# UBX_NORA_B1_SCHEM_0003_Shield_Conn.net
KiCad netlist of a schematic drawn in Altium Designer
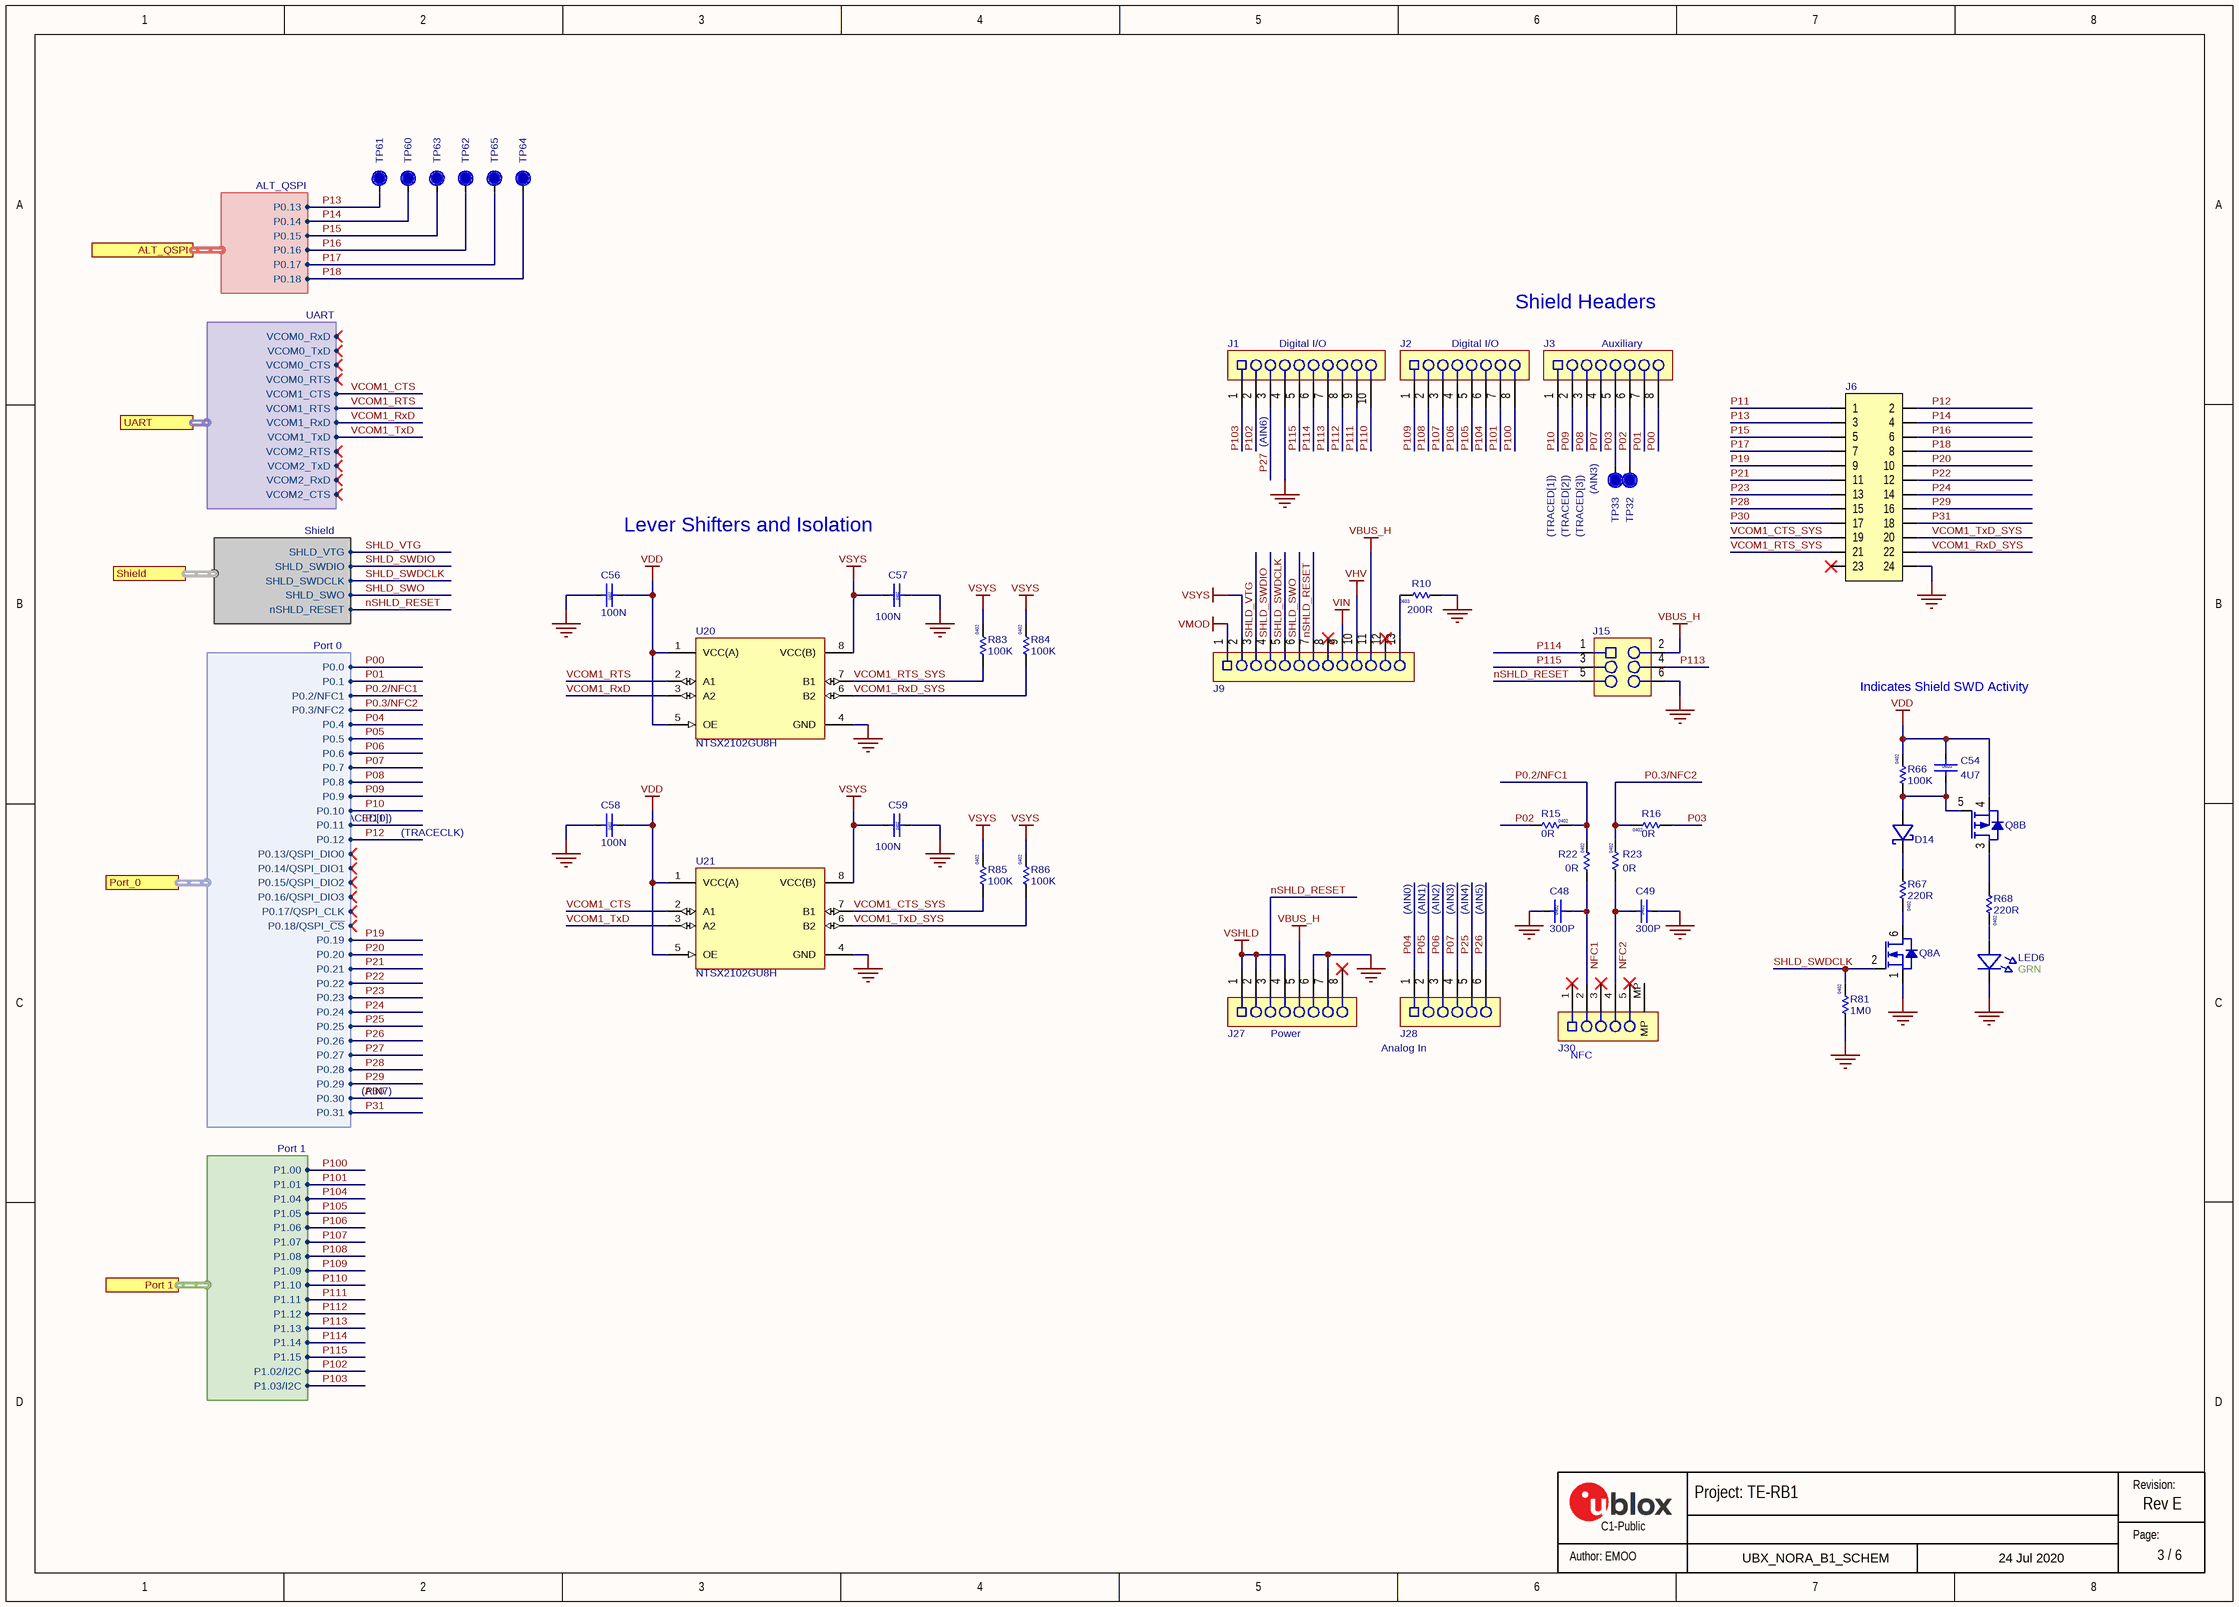
[diagram p0: UBX_NORA_B1_SCHEM_0003_Shield_Conn.SchDoc]

(export (version "E")
  (design (tool "Eeschema 10.0.6"))
  (components
    (comp (ref "C48")
      (value "300P")
      (footprint "Cap 0402 HD")
      (description "CAP CER C0G 0402 300P 50V")
      (fields
        (field (name "SIZE") "0402")
        (field (name "PART NUMBER") "UBXH01-0000594")
        (field (name "MANUFACTURER") "Murata Manufacturing Company, Ltd.")
        (field (name "EDITOR") "eric.moog")
      )
      (libsource (lib "UBX_Parts_DB_Lib") (part "Cap Chip"))
    )
    (comp (ref "C49")
      (value "300P")
      (footprint "Cap 0402 HD")
      (description "CAP CER C0G 0402 300P 50V")
      (fields
        (field (name "SIZE") "0402")
        (field (name "PART NUMBER") "UBXH01-0000594")
        (field (name "MANUFACTURER") "Murata Manufacturing Company, Ltd.")
        (field (name "EDITOR") "eric.moog")
      )
      (libsource (lib "UBX_Parts_DB_Lib") (part "Cap Chip"))
    )
    (comp (ref "C54")
      (value "4U7")
      (footprint "CAP 0603 HD")
      (description "CAP CER X5R 0603 4U7 10% 6.3V")
      (fields
        (field (name "SIZE") "0603")
        (field (name "PART NUMBER") "UBXH01-2002003")
        (field (name "TOLERANCE") "10%")
        (field (name "EDITOR") "philippe.largier")
        (field (name "RELEASED BY") "roland.rust")
      )
      (libsource (lib "UBX_Parts_DB_Lib") (part "Cap Chip"))
    )
    (comp (ref "C56")
      (value "100N")
      (footprint "Cap 0402 HD")
      (description "CAP CER X5R 0402 100N 10% 10V")
      (fields
        (field (name "SIZE") "0402")
        (field (name "PART NUMBER") "UBXH01-2021002")
        (field (name "TOLERANCE") "10%")
        (field (name "EDITOR") "roland.rust")
        (field (name "RELEASED BY") "roland.rust")
      )
      (libsource (lib "UBX_Parts_DB_Lib") (part "Cap Chip"))
    )
    (comp (ref "C57")
      (value "100N")
      (footprint "Cap 0402 HD")
      (description "CAP CER X5R 0402 100N 10% 10V")
      (fields
        (field (name "SIZE") "0402")
        (field (name "PART NUMBER") "UBXH01-2021002")
        (field (name "TOLERANCE") "10%")
        (field (name "EDITOR") "roland.rust")
        (field (name "RELEASED BY") "roland.rust")
      )
      (libsource (lib "UBX_Parts_DB_Lib") (part "Cap Chip"))
    )
    (comp (ref "C58")
      (value "100N")
      (footprint "Cap 0402 HD")
      (description "CAP CER X5R 0402 100N 10% 10V")
      (fields
        (field (name "SIZE") "0402")
        (field (name "PART NUMBER") "UBXH01-2021002")
        (field (name "TOLERANCE") "10%")
        (field (name "EDITOR") "roland.rust")
        (field (name "RELEASED BY") "roland.rust")
      )
      (libsource (lib "UBX_Parts_DB_Lib") (part "Cap Chip"))
    )
    (comp (ref "C59")
      (value "100N")
      (footprint "Cap 0402 HD")
      (description "CAP CER X5R 0402 100N 10% 10V")
      (fields
        (field (name "SIZE") "0402")
        (field (name "PART NUMBER") "UBXH01-2021002")
        (field (name "TOLERANCE") "10%")
        (field (name "EDITOR") "roland.rust")
        (field (name "RELEASED BY") "roland.rust")
      )
      (libsource (lib "UBX_Parts_DB_Lib") (part "Cap Chip"))
    )
    (comp (ref "D14")
      (value "UBXH07-0000039")
      (footprint "SOD-523")
      (description "SCHOTTKY BARRIER DIODE 30V 200mA")
      (fields
        (field (name "MANUFACTURER") "ON Semiconductor")
        (field (name "EDITOR") "matej.budin")
        (field (name "RELEASED BY") "pierpaolo.arban")
      )
      (libsource (lib "UBX_Parts_DB_Lib") (part "Diode_Schottky"))
    )
    (comp (ref "J1")
      (value "UBXH04-0000788")
      (footprint "SKT-0.1P-SSM-110-L-SV")
      (description "10 -PIN RECEPTACLE BOTTOM OR TOP ENTRY VERT 2.54MM 50V 2.5A")
      (fields (field (name "MANUFACTURER") "Amphenol Corporation") (field (name "EDITOR") "eric.moog"))
      (libsource (lib "UBX_Parts_DB_Lib") (part "CON-10Pin_1Row"))
    )
    (comp (ref "J2")
      (value "UBXH04-0000789")
      (footprint "SKT-0.1P-SSM-108-L-SV")
      (description "8 -PIN RECEPTACLE BOTTOM OR TOP ENTRY VERT 2.54MM 50V 2.5A")
      (fields (field (name "MANUFACTURER") "Amphenol Corporation") (field (name "EDITOR") "eric.moog"))
      (libsource (lib "UBX_Parts_DB_Lib") (part "CON-8Pin_1Row"))
    )
    (comp (ref "J3")
      (value "UBXH04-0000789")
      (footprint "SKT-0.1P-SSM-108-L-SV")
      (description "8 -PIN RECEPTACLE BOTTOM OR TOP ENTRY VERT 2.54MM 50V 2.5A")
      (fields (field (name "MANUFACTURER") "Amphenol Corporation") (field (name "EDITOR") "eric.moog"))
      (libsource (lib "UBX_Parts_DB_Lib") (part "CON-8Pin_1Row"))
    )
    (comp (ref "J6")
      (value "SSM-112-F-DV")
      (footprint "SSM-112-F-DV")
      (description "2-ROW SMD PCB CONN SOCKET 100MIL GRID 24-PIN 0.64MM SQUARE 405V 5.2A")
      (fields
        (field (name "PART NUMBER") "UBXH04-0000802")
        (field (name "MANUFACTURER") "Samtec")
        (field (name "EDITOR") "eric.moog")
      )
      (libsource (lib "UBX_Parts_DB_Lib") (part "SSM-112-F-DV"))
    )
    (comp (ref "J9")
      (value "UBXH04-0000801")
      (footprint "TSM-113-01-L-SV")
      (description "1-ROW SMD-PCB CONN 13 -PIN 2.54MM STRIP 475V 4.1A")
      (fields (field (name "MANUFACTURER") "Samtec") (field (name "EDITOR") "eric.moog"))
      (libsource (lib "UBX_Parts_DB_Lib") (part "CON-13Pin_1Row"))
    )
    (comp (ref "J15")
      (value "UBXH04-0000805")
      (footprint "HDR-0.1P-6Pin-3x2-SMT")
      (description "2-ROW CONN SMD VERT 2X06 PIN 2.54MM 100V 2A")
      (fields (field (name "MANUFACTURER") "molex") (field (name "EDITOR") "eric.moog"))
      (libsource (lib "UBX_Parts_DB_Lib") (part "CON-6Pin_2Row"))
    )
    (comp (ref "J27")
      (value "UBXH04-0000789")
      (footprint "SKT-0.1P-SSM-108-L-SV")
      (description "8 -PIN RECEPTACLE BOTTOM OR TOP ENTRY VERT 2.54MM 50V 2.5A")
      (fields (field (name "MANUFACTURER") "Amphenol Corporation") (field (name "EDITOR") "eric.moog"))
      (libsource (lib "") (part "CON-8Pin_1Row_1"))
    )
    (comp (ref "J28")
      (value "UBXH04-0000790")
      (footprint "SKT-0.1P-SSM-106-L-SV")
      (description "6 -PIN RECEPTACLE BOTTOM OR TOP ENTRY VERT 2.54MM 50V 2.5A")
      (fields (field (name "MANUFACTURER") "Amphenol Corporation") (field (name "EDITOR") "eric.moog"))
      (libsource (lib "UBX_Parts_DB_Lib") (part "CON-6Pin_1Row"))
    )
    (comp (ref "J30")
      (value "UBXH04-0000800")
      (footprint "Molex 051281-0594")
      (description "CONN NON ZIF FPC MOLEX 51281 0.5MM PITCH 5-PIN TOP AND BOTTOM 50V 500mA")
      (fields
        (field (name "VOLTAGE") "50V")
        (field (name "MANUFACTURER") "molex")
        (field (name "EDITOR") "eric.moog")
      )
      (libsource (lib "UBX_Parts_DB_Lib") (part "CON-5Pin_1Row-046284005001846"))
    )
    (comp (ref "LED6")
      (value "UBXH11-0000001")
      (footprint "LED_0603_GREEN")
      (description "LED SMD 0603 GREEN 2.5V 20mA")
      (fields
        (field (name "COLOR") "GRN")
        (field (name "MANUFACTURER") "Kingbright")
        (field (name "EDITOR") "gianni.falleroni")
        (field (name "RELEASED BY") "alex.claville")
      )
      (libsource (lib "UBX_Parts_DB_Lib") (part "LED_BASE"))
    )
    (comp (ref "Q8")
      (value "UBXH20-0000084")
      (footprint "SOT-563")
      (description "SMALL SIGNAL COMPLEMENTARY W/ ESD PROTECTION MOSFET SOT-563-6 PACKAGE")
      (fields
        (field (name "MANUFACTURER") "ON Semiconductor")
        (field (name "EDITOR") "pierpaolo.arban")
        (field (name "RELEASED BY") "matej.budin")
      )
      (libsource (lib "UBX_Parts_DB_Lib") (part "MOSFET-N-P_Pair"))
    )
    (comp (ref "R10")
      (value "200R")
      (footprint "RES 0603 HD")
      (description "RES THICK FILM CHIP 0603 200R 5% 100mW")
      (fields
        (field (name "SIZE") "0603")
        (field (name "PART NUMBER") "UBXH18-0007056")
        (field (name "TOLERANCE") "5%")
        (field (name "EDITOR") "andreas.thiel")
      )
      (libsource (lib "UBX_Parts_DB_Lib") (part "Res sm"))
    )
    (comp (ref "R15")
      (value "0R")
      (footprint "RES 0402 HD")
      (description "RES THICK FILM CHIP 0402 0R 0 100mW")
      (fields
        (field (name "SIZE") "0402")
        (field (name "PART NUMBER") "UBXH18-0003002")
        (field (name "TOLERANCE") "0")
        (field (name "EDITOR") "charlotte.biber")
        (field (name "RELEASED BY") "peter.mueller")
      )
      (libsource (lib "UBX_Parts_DB_Lib") (part "Res sm"))
    )
    (comp (ref "R16")
      (value "0R")
      (footprint "RES 0402 HD")
      (description "RES THICK FILM CHIP 0402 0R 0 100mW")
      (fields
        (field (name "SIZE") "0402")
        (field (name "PART NUMBER") "UBXH18-0003002")
        (field (name "TOLERANCE") "0")
        (field (name "EDITOR") "charlotte.biber")
        (field (name "RELEASED BY") "peter.mueller")
      )
      (libsource (lib "UBX_Parts_DB_Lib") (part "Res sm"))
    )
    (comp (ref "R22")
      (value "0R")
      (footprint "RES 0402 HD")
      (description "RES THICK FILM CHIP 0402 0R 0 100mW")
      (fields
        (field (name "SIZE") "0402")
        (field (name "PART NUMBER") "UBXH18-0003002")
        (field (name "TOLERANCE") "0")
        (field (name "EDITOR") "charlotte.biber")
        (field (name "RELEASED BY") "peter.mueller")
      )
      (libsource (lib "UBX_Parts_DB_Lib") (part "Res sm"))
    )
    (comp (ref "R23")
      (value "0R")
      (footprint "RES 0402 HD")
      (description "RES THICK FILM CHIP 0402 0R 0 100mW")
      (fields
        (field (name "SIZE") "0402")
        (field (name "PART NUMBER") "UBXH18-0003002")
        (field (name "TOLERANCE") "0")
        (field (name "EDITOR") "charlotte.biber")
        (field (name "RELEASED BY") "peter.mueller")
      )
      (libsource (lib "UBX_Parts_DB_Lib") (part "Res sm"))
    )
    (comp (ref "R66")
      (value "100K")
      (footprint "RES 0402 HD")
      (description "RES THICK FILM CHIP 0402 100K 1% 63mW")
      (fields
        (field (name "SIZE") "0402")
        (field (name "PART NUMBER") "UBXH18-0000005")
        (field (name "TOLERANCE") "1%")
        (field (name "EDITOR") "dario.antonaz")
        (field (name "RELEASED BY") "sandro.sestan")
      )
      (libsource (lib "UBX_Parts_DB_Lib") (part "Res sm"))
    )
    (comp (ref "R67")
      (value "220R")
      (footprint "RES 0402 HD")
      (description "RES THICK FILM CHIP 0402 220R 5% 100mW")
      (fields
        (field (name "SIZE") "0402")
        (field (name "PART NUMBER") "UBXH18-0008033")
        (field (name "TOLERANCE") "5%")
        (field (name "EDITOR") "roland.rust")
        (field (name "RELEASED BY") "roland.rust")
      )
      (libsource (lib "UBX_Parts_DB_Lib") (part "Res sm"))
    )
    (comp (ref "R68")
      (value "220R")
      (footprint "RES 0402 HD")
      (description "RES THICK FILM CHIP 0402 220R 5% 100mW")
      (fields
        (field (name "SIZE") "0402")
        (field (name "PART NUMBER") "UBXH18-0008033")
        (field (name "TOLERANCE") "5%")
        (field (name "EDITOR") "roland.rust")
        (field (name "RELEASED BY") "roland.rust")
      )
      (libsource (lib "UBX_Parts_DB_Lib") (part "Res sm"))
    )
    (comp (ref "R81")
      (value "1M0")
      (footprint "RES 0402 HD")
      (description "RES THICK FILM CHIP 0402 1M0 5% 63mW")
      (fields
        (field (name "SIZE") "0402")
        (field (name "PART NUMBER") "UBXH18-0008121")
        (field (name "TOLERANCE") "5%")
        (field (name "EDITOR") "daniel.hurni")
        (field (name "RELEASED BY") "doris.zahnd")
      )
      (libsource (lib "UBX_Parts_DB_Lib") (part "Res sm"))
    )
    (comp (ref "R83")
      (value "100K")
      (footprint "RES 0402 HD")
      (description "RES THICK FILM CHIP 0402 100K 1% 63mW")
      (fields
        (field (name "SIZE") "0402")
        (field (name "PART NUMBER") "UBXH18-0000005")
        (field (name "TOLERANCE") "1%")
        (field (name "EDITOR") "dario.antonaz")
        (field (name "RELEASED BY") "sandro.sestan")
      )
      (libsource (lib "UBX_Parts_DB_Lib") (part "Res sm"))
    )
    (comp (ref "R84")
      (value "100K")
      (footprint "RES 0402 HD")
      (description "RES THICK FILM CHIP 0402 100K 1% 63mW")
      (fields
        (field (name "SIZE") "0402")
        (field (name "PART NUMBER") "UBXH18-0000005")
        (field (name "TOLERANCE") "1%")
        (field (name "EDITOR") "dario.antonaz")
        (field (name "RELEASED BY") "sandro.sestan")
      )
      (libsource (lib "UBX_Parts_DB_Lib") (part "Res sm"))
    )
    (comp (ref "R85")
      (value "100K")
      (footprint "RES 0402 HD")
      (description "RES THICK FILM CHIP 0402 100K 1% 63mW")
      (fields
        (field (name "SIZE") "0402")
        (field (name "PART NUMBER") "UBXH18-0000005")
        (field (name "TOLERANCE") "1%")
        (field (name "EDITOR") "dario.antonaz")
        (field (name "RELEASED BY") "sandro.sestan")
      )
      (libsource (lib "UBX_Parts_DB_Lib") (part "Res sm"))
    )
    (comp (ref "R86")
      (value "100K")
      (footprint "RES 0402 HD")
      (description "RES THICK FILM CHIP 0402 100K 1% 63mW")
      (fields
        (field (name "SIZE") "0402")
        (field (name "PART NUMBER") "UBXH18-0000005")
        (field (name "TOLERANCE") "1%")
        (field (name "EDITOR") "dario.antonaz")
        (field (name "RELEASED BY") "sandro.sestan")
      )
      (libsource (lib "UBX_Parts_DB_Lib") (part "Res sm"))
    )
    (comp (ref "TP32")
      (value "TP")
      (footprint "TP10R")
      (description "TESTPOINT 1MM CIRCULAR")
      (fields (field (name "PART NUMBER") "UBXH00-0000096") (field (name "EDITOR") "eric.moog"))
      (libsource (lib "UBX_Parts_DB_Lib") (part "TP_R"))
    )
    (comp (ref "TP33")
      (value "TP")
      (footprint "TP10R")
      (description "TESTPOINT 1MM CIRCULAR")
      (fields (field (name "PART NUMBER") "UBXH00-0000096") (field (name "EDITOR") "eric.moog"))
      (libsource (lib "UBX_Parts_DB_Lib") (part "TP_R"))
    )
    (comp (ref "TP60")
      (value "TP")
      (footprint "TP10R")
      (description "TESTPOINT 1MM CIRCULAR")
      (fields (field (name "PART NUMBER") "UBXH00-0000096") (field (name "EDITOR") "eric.moog"))
      (libsource (lib "UBX_Parts_DB_Lib") (part "TP_R"))
    )
    (comp (ref "TP61")
      (value "TP")
      (footprint "TP10R")
      (description "TESTPOINT 1MM CIRCULAR")
      (fields (field (name "PART NUMBER") "UBXH00-0000096") (field (name "EDITOR") "eric.moog"))
      (libsource (lib "UBX_Parts_DB_Lib") (part "TP_R"))
    )
    (comp (ref "TP62")
      (value "TP")
      (footprint "TP10R")
      (description "TESTPOINT 1MM CIRCULAR")
      (fields (field (name "PART NUMBER") "UBXH00-0000096") (field (name "EDITOR") "eric.moog"))
      (libsource (lib "UBX_Parts_DB_Lib") (part "TP_R"))
    )
    (comp (ref "TP63")
      (value "TP")
      (footprint "TP10R")
      (description "TESTPOINT 1MM CIRCULAR")
      (fields (field (name "PART NUMBER") "UBXH00-0000096") (field (name "EDITOR") "eric.moog"))
      (libsource (lib "UBX_Parts_DB_Lib") (part "TP_R"))
    )
    (comp (ref "TP64")
      (value "TP")
      (footprint "TP10R")
      (description "TESTPOINT 1MM CIRCULAR")
      (fields (field (name "PART NUMBER") "UBXH00-0000096") (field (name "EDITOR") "eric.moog"))
      (libsource (lib "UBX_Parts_DB_Lib") (part "TP_R"))
    )
    (comp (ref "TP65")
      (value "TP")
      (footprint "TP10R")
      (description "TESTPOINT 1MM CIRCULAR")
      (fields (field (name "PART NUMBER") "UBXH00-0000096") (field (name "EDITOR") "eric.moog"))
      (libsource (lib "UBX_Parts_DB_Lib") (part "TP_R"))
    )
    (comp (ref "U20")
      (value "UBXH10-0000106")
      (footprint "QFN0.4P3x1-8Pin")
      (description "2-BIT BIDIRECTIONAL TRANSLATING TRANSCEIVER AUTO DIRECTION SENSING OPEN DRAIN XQFN8 5.5V")
      (fields
        (field (name "VOLTAGE") "5.5V")
        (field (name "MANUFACTURER PART NUMBER 1") "NTSX2102GU8H")
        (field (name "MANUFACTURER") "NXP")
        (field (name "EDITOR") "eric.moog")
      )
      (libsource (lib "UBX_Parts_DB_Lib") (part "NTSX2102GU8"))
    )
    (comp (ref "U21")
      (value "UBXH10-0000106")
      (footprint "QFN0.4P3x1-8Pin")
      (description "2-BIT BIDIRECTIONAL TRANSLATING TRANSCEIVER AUTO DIRECTION SENSING OPEN DRAIN XQFN8 5.5V")
      (fields
        (field (name "VOLTAGE") "5.5V")
        (field (name "MANUFACTURER PART NUMBER 1") "NTSX2102GU8H")
        (field (name "MANUFACTURER") "NXP")
        (field (name "EDITOR") "eric.moog")
      )
      (libsource (lib "UBX_Parts_DB_Lib") (part "NTSX2102GU8"))
    )
  )
  (nets
    (net (code "7") (name "/NFC1") (class "Default")
      (node (ref "C48") (pin "2") (pinfunction "2_2") (pintype "passive"))
      (node (ref "J30") (pin "2") (pinfunction "2_2") (pintype "passive"))
      (node (ref "R22") (pin "1") (pinfunction "1_1") (pintype "passive"))
    )
    (net (code "8") (name "/NFC2") (class "Default")
      (node (ref "C49") (pin "1") (pinfunction "1_1") (pintype "passive"))
      (node (ref "J30") (pin "4") (pinfunction "4_4") (pintype "passive"))
      (node (ref "R23") (pin "1") (pinfunction "1_1") (pintype "passive"))
    )
    (net (code "9") (name "/P00") (class "Default") (node (ref "J3") (pin "8") (pintype "passive")))
    (net (code "10") (name "/P0.2{slash}NFC1") (class "Default")
      (node (ref "R15") (pin "2") (pinfunction "2_2") (pintype "passive"))
      (node (ref "R22") (pin "2") (pinfunction "2_2") (pintype "passive"))
    )
    (net (code "11") (name "/P0.3{slash}NFC2") (class "Default")
      (node (ref "R16") (pin "2") (pinfunction "2_2") (pintype "passive"))
      (node (ref "R23") (pin "2") (pinfunction "2_2") (pintype "passive"))
    )
    (net (code "12") (name "/P01") (class "Default") (node (ref "J3") (pin "7") (pintype "passive")))
    (net (code "13") (name "/P02") (class "Default")
      (node (ref "J3") (pin "6") (pintype "passive"))
      (node (ref "R15") (pin "1") (pinfunction "1_1") (pintype "passive"))
      (node (ref "TP32") (pin "1") (pintype "passive"))
    )
    (net (code "14") (name "/P03") (class "Default")
      (node (ref "J3") (pin "5") (pintype "passive"))
      (node (ref "R16") (pin "1") (pinfunction "1_1") (pintype "passive"))
      (node (ref "TP33") (pin "1") (pintype "passive"))
    )
    (net (code "15") (name "/P04") (class "Default")
      (node (ref "J28") (pin "1") (pinfunction "1_1") (pintype "passive"))
    )
    (net (code "16") (name "/P05") (class "Default")
      (node (ref "J28") (pin "2") (pinfunction "2_2") (pintype "passive"))
    )
    (net (code "17") (name "/P06") (class "Default")
      (node (ref "J28") (pin "3") (pinfunction "3_3") (pintype "passive"))
    )
    (net (code "18") (name "/P07") (class "Default")
      (node (ref "J28") (pin "4") (pinfunction "4_4") (pintype "passive"))
      (node (ref "J3") (pin "4") (pintype "passive"))
    )
    (net (code "19") (name "/P08") (class "Default") (node (ref "J3") (pin "3") (pintype "passive")))
    (net (code "20") (name "/P09") (class "Default") (node (ref "J3") (pin "2") (pintype "passive")))
    (net (code "21") (name "/P10") (class "Default") (node (ref "J3") (pin "1") (pintype "passive")))
    (net (code "22") (name "/P11") (class "Default")
      (node (ref "J6") (pin "1") (pinfunction "1_1") (pintype "passive"))
    )
    (net (code "23") (name "/P12") (class "Default")
      (node (ref "J6") (pin "2") (pinfunction "2_2") (pintype "passive"))
    )
    (net (code "24") (name "/P13") (class "Default")
      (node (ref "J6") (pin "3") (pinfunction "3_3") (pintype "passive"))
      (node (ref "TP61") (pin "1") (pintype "passive"))
    )
    (net (code "25") (name "/P14") (class "Default")
      (node (ref "J6") (pin "4") (pinfunction "4_4") (pintype "passive"))
      (node (ref "TP60") (pin "1") (pintype "passive"))
    )
    (net (code "26") (name "/P15") (class "Default")
      (node (ref "J6") (pin "5") (pinfunction "5_5") (pintype "passive"))
      (node (ref "TP63") (pin "1") (pintype "passive"))
    )
    (net (code "27") (name "/P16") (class "Default")
      (node (ref "J6") (pin "6") (pinfunction "6_6") (pintype "passive"))
      (node (ref "TP62") (pin "1") (pintype "passive"))
    )
    (net (code "28") (name "/P17") (class "Default")
      (node (ref "J6") (pin "7") (pinfunction "7_7") (pintype "passive"))
      (node (ref "TP65") (pin "1") (pintype "passive"))
    )
    (net (code "29") (name "/P18") (class "Default")
      (node (ref "J6") (pin "8") (pinfunction "8_8") (pintype "passive"))
      (node (ref "TP64") (pin "1") (pintype "passive"))
    )
    (net (code "30") (name "/P19") (class "Default")
      (node (ref "J6") (pin "9") (pinfunction "9_9") (pintype "passive"))
    )
    (net (code "31") (name "/P20") (class "Default")
      (node (ref "J6") (pin "10") (pinfunction "10_10") (pintype "passive"))
    )
    (net (code "32") (name "/P21") (class "Default")
      (node (ref "J6") (pin "11") (pinfunction "11_11") (pintype "passive"))
    )
    (net (code "33") (name "/P22") (class "Default")
      (node (ref "J6") (pin "12") (pinfunction "12_12") (pintype "passive"))
    )
    (net (code "34") (name "/P23") (class "Default")
      (node (ref "J6") (pin "13") (pinfunction "13_13") (pintype "passive"))
    )
    (net (code "35") (name "/P24") (class "Default")
      (node (ref "J6") (pin "14") (pinfunction "14_14") (pintype "passive"))
    )
    (net (code "36") (name "/P25") (class "Default")
      (node (ref "J28") (pin "5") (pinfunction "5_5") (pintype "passive"))
    )
    (net (code "37") (name "/P26") (class "Default")
      (node (ref "J28") (pin "6") (pinfunction "6_6") (pintype "passive"))
    )
    (net (code "38") (name "/P27") (class "Default") (node (ref "J1") (pin "3") (pintype "passive")))
    (net (code "39") (name "/P28") (class "Default")
      (node (ref "J6") (pin "15") (pinfunction "15_15") (pintype "passive"))
    )
    (net (code "40") (name "/P29") (class "Default")
      (node (ref "J6") (pin "16") (pinfunction "16_16") (pintype "passive"))
    )
    (net (code "41") (name "/P30") (class "Default")
      (node (ref "J6") (pin "17") (pinfunction "17_17") (pintype "passive"))
    )
    (net (code "42") (name "/P31") (class "Default")
      (node (ref "J6") (pin "18") (pinfunction "18_18") (pintype "passive"))
    )
    (net (code "43") (name "/P100") (class "Default") (node (ref "J2") (pin "8") (pintype "passive")))
    (net (code "44") (name "/P101") (class "Default") (node (ref "J2") (pin "7") (pintype "passive")))
    (net (code "45") (name "/P102") (class "Default") (node (ref "J1") (pin "2") (pintype "passive")))
    (net (code "46") (name "/P103") (class "Default") (node (ref "J1") (pin "1") (pintype "passive")))
    (net (code "47") (name "/P104") (class "Default") (node (ref "J2") (pin "6") (pintype "passive")))
    (net (code "48") (name "/P105") (class "Default") (node (ref "J2") (pin "5") (pintype "passive")))
    (net (code "49") (name "/P106") (class "Default") (node (ref "J2") (pin "4") (pintype "passive")))
    (net (code "50") (name "/P107") (class "Default") (node (ref "J2") (pin "3") (pintype "passive")))
    (net (code "51") (name "/P108") (class "Default") (node (ref "J2") (pin "2") (pintype "passive")))
    (net (code "52") (name "/P109") (class "Default") (node (ref "J2") (pin "1") (pintype "passive")))
    (net (code "53") (name "/P110") (class "Default") (node (ref "J1") (pin "10") (pintype "passive")))
    (net (code "54") (name "/P111") (class "Default") (node (ref "J1") (pin "9") (pintype "passive")))
    (net (code "55") (name "/P112") (class "Default") (node (ref "J1") (pin "8") (pintype "passive")))
    (net (code "56") (name "/P113") (class "Default")
      (node (ref "J1") (pin "7") (pintype "passive"))
      (node (ref "J15") (pin "4") (pintype "passive"))
    )
    (net (code "57") (name "/P114") (class "Default")
      (node (ref "J1") (pin "6") (pintype "passive"))
      (node (ref "J15") (pin "1") (pintype "passive"))
    )
    (net (code "58") (name "/P115") (class "Default")
      (node (ref "J1") (pin "5") (pintype "passive"))
      (node (ref "J15") (pin "3") (pintype "passive"))
    )
    (net (code "59") (name "/SHLD_SWDCLK") (class "Default")
      (node (ref "J9") (pin "5") (pintype "passive"))
      (node (ref "Q8") (pin "2") (pinfunction "G1_2") (pintype "passive"))
      (node (ref "R81") (pin "2") (pinfunction "2_2") (pintype "passive"))
    )
    (net (code "60") (name "/SHLD_SWDIO") (class "Default") (node (ref "J9") (pin "4") (pintype "passive")))
    (net (code "61") (name "/SHLD_SWO") (class "Default") (node (ref "J9") (pin "6") (pintype "passive")))
    (net (code "62") (name "/SHLD_VTG") (class "Default") (node (ref "J9") (pin "3") (pintype "passive")))
    (net (code "63") (name "/VCOM1_CTS") (class "Default")
      (node (ref "U21") (pin "2") (pinfunction "A1_2") (pintype "bidirectional"))
    )
    (net (code "64") (name "/VCOM1_CTS_SYS") (class "Default")
      (node (ref "J6") (pin "19") (pinfunction "19_19") (pintype "passive"))
      (node (ref "R85") (pin "1") (pinfunction "1_1") (pintype "passive"))
      (node (ref "U21") (pin "7") (pinfunction "B1_7") (pintype "bidirectional"))
    )
    (net (code "65") (name "/VCOM1_RTS") (class "Default")
      (node (ref "U20") (pin "2") (pinfunction "A1_2") (pintype "bidirectional"))
    )
    (net (code "66") (name "/VCOM1_RTS_SYS") (class "Default")
      (node (ref "J6") (pin "21") (pinfunction "21_21") (pintype "passive"))
      (node (ref "R83") (pin "1") (pinfunction "1_1") (pintype "passive"))
      (node (ref "U20") (pin "7") (pinfunction "B1_7") (pintype "bidirectional"))
    )
    (net (code "67") (name "/VCOM1_RxD") (class "Default")
      (node (ref "U20") (pin "3") (pinfunction "A2_3") (pintype "bidirectional"))
    )
    (net (code "68") (name "/VCOM1_RxD_SYS") (class "Default")
      (node (ref "J6") (pin "22") (pinfunction "22_22") (pintype "passive"))
      (node (ref "R84") (pin "1") (pinfunction "1_1") (pintype "passive"))
      (node (ref "U20") (pin "6") (pinfunction "B2_6") (pintype "bidirectional"))
    )
    (net (code "69") (name "/VCOM1_TxD") (class "Default")
      (node (ref "U21") (pin "3") (pinfunction "A2_3") (pintype "bidirectional"))
    )
    (net (code "70") (name "/VCOM1_TxD_SYS") (class "Default")
      (node (ref "J6") (pin "20") (pinfunction "20_20") (pintype "passive"))
      (node (ref "R86") (pin "1") (pinfunction "1_1") (pintype "passive"))
      (node (ref "U21") (pin "6") (pinfunction "B2_6") (pintype "bidirectional"))
    )
    (net (code "71") (name "/nSHLD_RESET") (class "Default")
      (node (ref "J15") (pin "5") (pintype "passive"))
      (node (ref "J27") (pin "3") (pintype "passive"))
      (node (ref "J9") (pin "7") (pintype "passive"))
    )
    (net (code "77") (name "GND") (class "Default")
      (node (ref "C48") (pin "1") (pinfunction "1_1") (pintype "passive"))
      (node (ref "C49") (pin "2") (pinfunction "2_2") (pintype "passive"))
      (node (ref "C56") (pin "2") (pinfunction "2_2") (pintype "passive"))
      (node (ref "C57") (pin "1") (pinfunction "1_1") (pintype "passive"))
      (node (ref "C58") (pin "2") (pinfunction "2_2") (pintype "passive"))
      (node (ref "C59") (pin "1") (pinfunction "1_1") (pintype "passive"))
      (node (ref "J1") (pin "4") (pintype "passive"))
      (node (ref "J15") (pin "6") (pintype "passive"))
      (node (ref "J27") (pin "6") (pintype "passive"))
      (node (ref "J27") (pin "7") (pintype "passive"))
      (node (ref "J6") (pin "24") (pinfunction "24_24") (pintype "passive"))
      (node (ref "LED6") (pin "1") (pinfunction "C_1") (pintype "passive"))
      (node (ref "Q8") (pin "1") (pinfunction "S1_1") (pintype "passive"))
      (node (ref "R10") (pin "1") (pinfunction "1_1") (pintype "passive"))
      (node (ref "R81") (pin "1") (pinfunction "1_1") (pintype "passive"))
      (node (ref "U20") (pin "4") (pinfunction "GND_4") (pintype "power_in"))
      (node (ref "U21") (pin "4") (pinfunction "GND_4") (pintype "power_in"))
    )
    (net (code "78") (name "Net-(D14-Anode)") (class "Default")
      (node (ref "C54") (pin "2") (pinfunction "2_2") (pintype "passive"))
      (node (ref "D14") (pin "A") (pinfunction "Anode_A") (pintype "passive"))
      (node (ref "Q8") (pin "5") (pinfunction "G2_5") (pintype "passive"))
      (node (ref "R66") (pin "1") (pinfunction "1_1") (pintype "passive"))
    )
    (net (code "79") (name "Net-(D14-Cathode)") (class "Default")
      (node (ref "D14") (pin "C") (pinfunction "Cathode_C") (pintype "passive"))
      (node (ref "R67") (pin "1") (pinfunction "1_1") (pintype "passive"))
    )
    (net (code "80") (name "Net-(J9-Pad13)") (class "Default")
      (node (ref "J9") (pin "13") (pintype "passive"))
      (node (ref "R10") (pin "2") (pinfunction "2_2") (pintype "passive"))
    )
    (net (code "81") (name "Net-(LED6-A)") (class "Default")
      (node (ref "LED6") (pin "2") (pinfunction "A_2") (pintype "passive"))
      (node (ref "R68") (pin "2") (pinfunction "2_2") (pintype "passive"))
    )
    (net (code "82") (name "Net-(Q8A-D1)") (class "Default")
      (node (ref "Q8") (pin "6") (pinfunction "D1_6") (pintype "passive"))
      (node (ref "R67") (pin "2") (pinfunction "2_2") (pintype "passive"))
    )
    (net (code "83") (name "Net-(Q8B-D2)") (class "Default")
      (node (ref "Q8") (pin "3") (pinfunction "D2_3") (pintype "passive"))
      (node (ref "R68") (pin "1") (pinfunction "1_1") (pintype "passive"))
    )
    (net (code "84") (name "VBUS_H") (class "Default")
      (node (ref "J15") (pin "2") (pintype "passive"))
      (node (ref "J27") (pin "5") (pintype "passive"))
      (node (ref "J9") (pin "11") (pintype "passive"))
    )
    (net (code "85") (name "VDD") (class "Default")
      (node (ref "C54") (pin "1") (pinfunction "1_1") (pintype "passive"))
      (node (ref "C56") (pin "1") (pinfunction "1_1") (pintype "passive"))
      (node (ref "C58") (pin "1") (pinfunction "1_1") (pintype "passive"))
      (node (ref "Q8") (pin "4") (pinfunction "S2_4") (pintype "passive"))
      (node (ref "R66") (pin "2") (pinfunction "2_2") (pintype "passive"))
      (node (ref "U20") (pin "1") (pinfunction "VCC(A)_1") (pintype "power_in"))
      (node (ref "U20") (pin "5") (pinfunction "OE_5") (pintype "input"))
      (node (ref "U21") (pin "1") (pinfunction "VCC(A)_1") (pintype "power_in"))
      (node (ref "U21") (pin "5") (pinfunction "OE_5") (pintype "input"))
    )
    (net (code "86") (name "VHV") (class "Default") (node (ref "J9") (pin "10") (pintype "passive")))
    (net (code "87") (name "VIN") (class "Default") (node (ref "J9") (pin "9") (pintype "passive")))
    (net (code "88") (name "VMOD") (class "Default") (node (ref "J9") (pin "1") (pintype "passive")))
    (net (code "89") (name "VSHLD") (class "Default")
      (node (ref "J27") (pin "1") (pintype "passive"))
      (node (ref "J27") (pin "2") (pintype "passive"))
      (node (ref "J27") (pin "4") (pintype "passive"))
    )
    (net (code "90") (name "VSYS") (class "Default")
      (node (ref "C57") (pin "2") (pinfunction "2_2") (pintype "passive"))
      (node (ref "C59") (pin "2") (pinfunction "2_2") (pintype "passive"))
      (node (ref "J9") (pin "2") (pintype "passive"))
      (node (ref "R83") (pin "2") (pinfunction "2_2") (pintype "passive"))
      (node (ref "R84") (pin "2") (pinfunction "2_2") (pintype "passive"))
      (node (ref "R85") (pin "2") (pinfunction "2_2") (pintype "passive"))
      (node (ref "R86") (pin "2") (pinfunction "2_2") (pintype "passive"))
      (node (ref "U20") (pin "8") (pinfunction "VCC(B)_8") (pintype "power_in"))
      (node (ref "U21") (pin "8") (pinfunction "VCC(B)_8") (pintype "power_in"))
    )
    (net (code "91") (name "unconnected-(J6-Pad23)") (class "Default")
      (node (ref "J6") (pin "23") (pinfunction "23_23") (pintype "passive+no_connect"))
    )
    (net (code "92") (name "unconnected-(J9-Pad8)") (class "Default")
      (node (ref "J9") (pin "8") (pintype "passive+no_connect"))
    )
    (net (code "93") (name "unconnected-(J9-Pad12)") (class "Default")
      (node (ref "J9") (pin "12") (pintype "passive+no_connect"))
    )
    (net (code "94") (name "unconnected-(J27-Pad8)") (class "Default")
      (node (ref "J27") (pin "8") (pintype "passive+no_connect"))
    )
    (net (code "95") (name "unconnected-(J30-Pad1)") (class "Default")
      (node (ref "J30") (pin "1") (pinfunction "1_1") (pintype "passive+no_connect"))
    )
    (net (code "96") (name "unconnected-(J30-Pad3)") (class "Default")
      (node (ref "J30") (pin "3") (pinfunction "3_3") (pintype "passive+no_connect"))
    )
    (net (code "97") (name "unconnected-(J30-Pad5)") (class "Default")
      (node (ref "J30") (pin "5") (pinfunction "5_5") (pintype "passive+no_connect"))
    )
    (net (code "98") (name "unconnected-(J30-PadMP)") (class "Default")
      (node (ref "J30") (pin "MP") (pinfunction "MP_MP") (pintype "passive"))
    )
  )
)
